# SYSTEM.net
KiCad netlist of a schematic drawn in Altium Designer
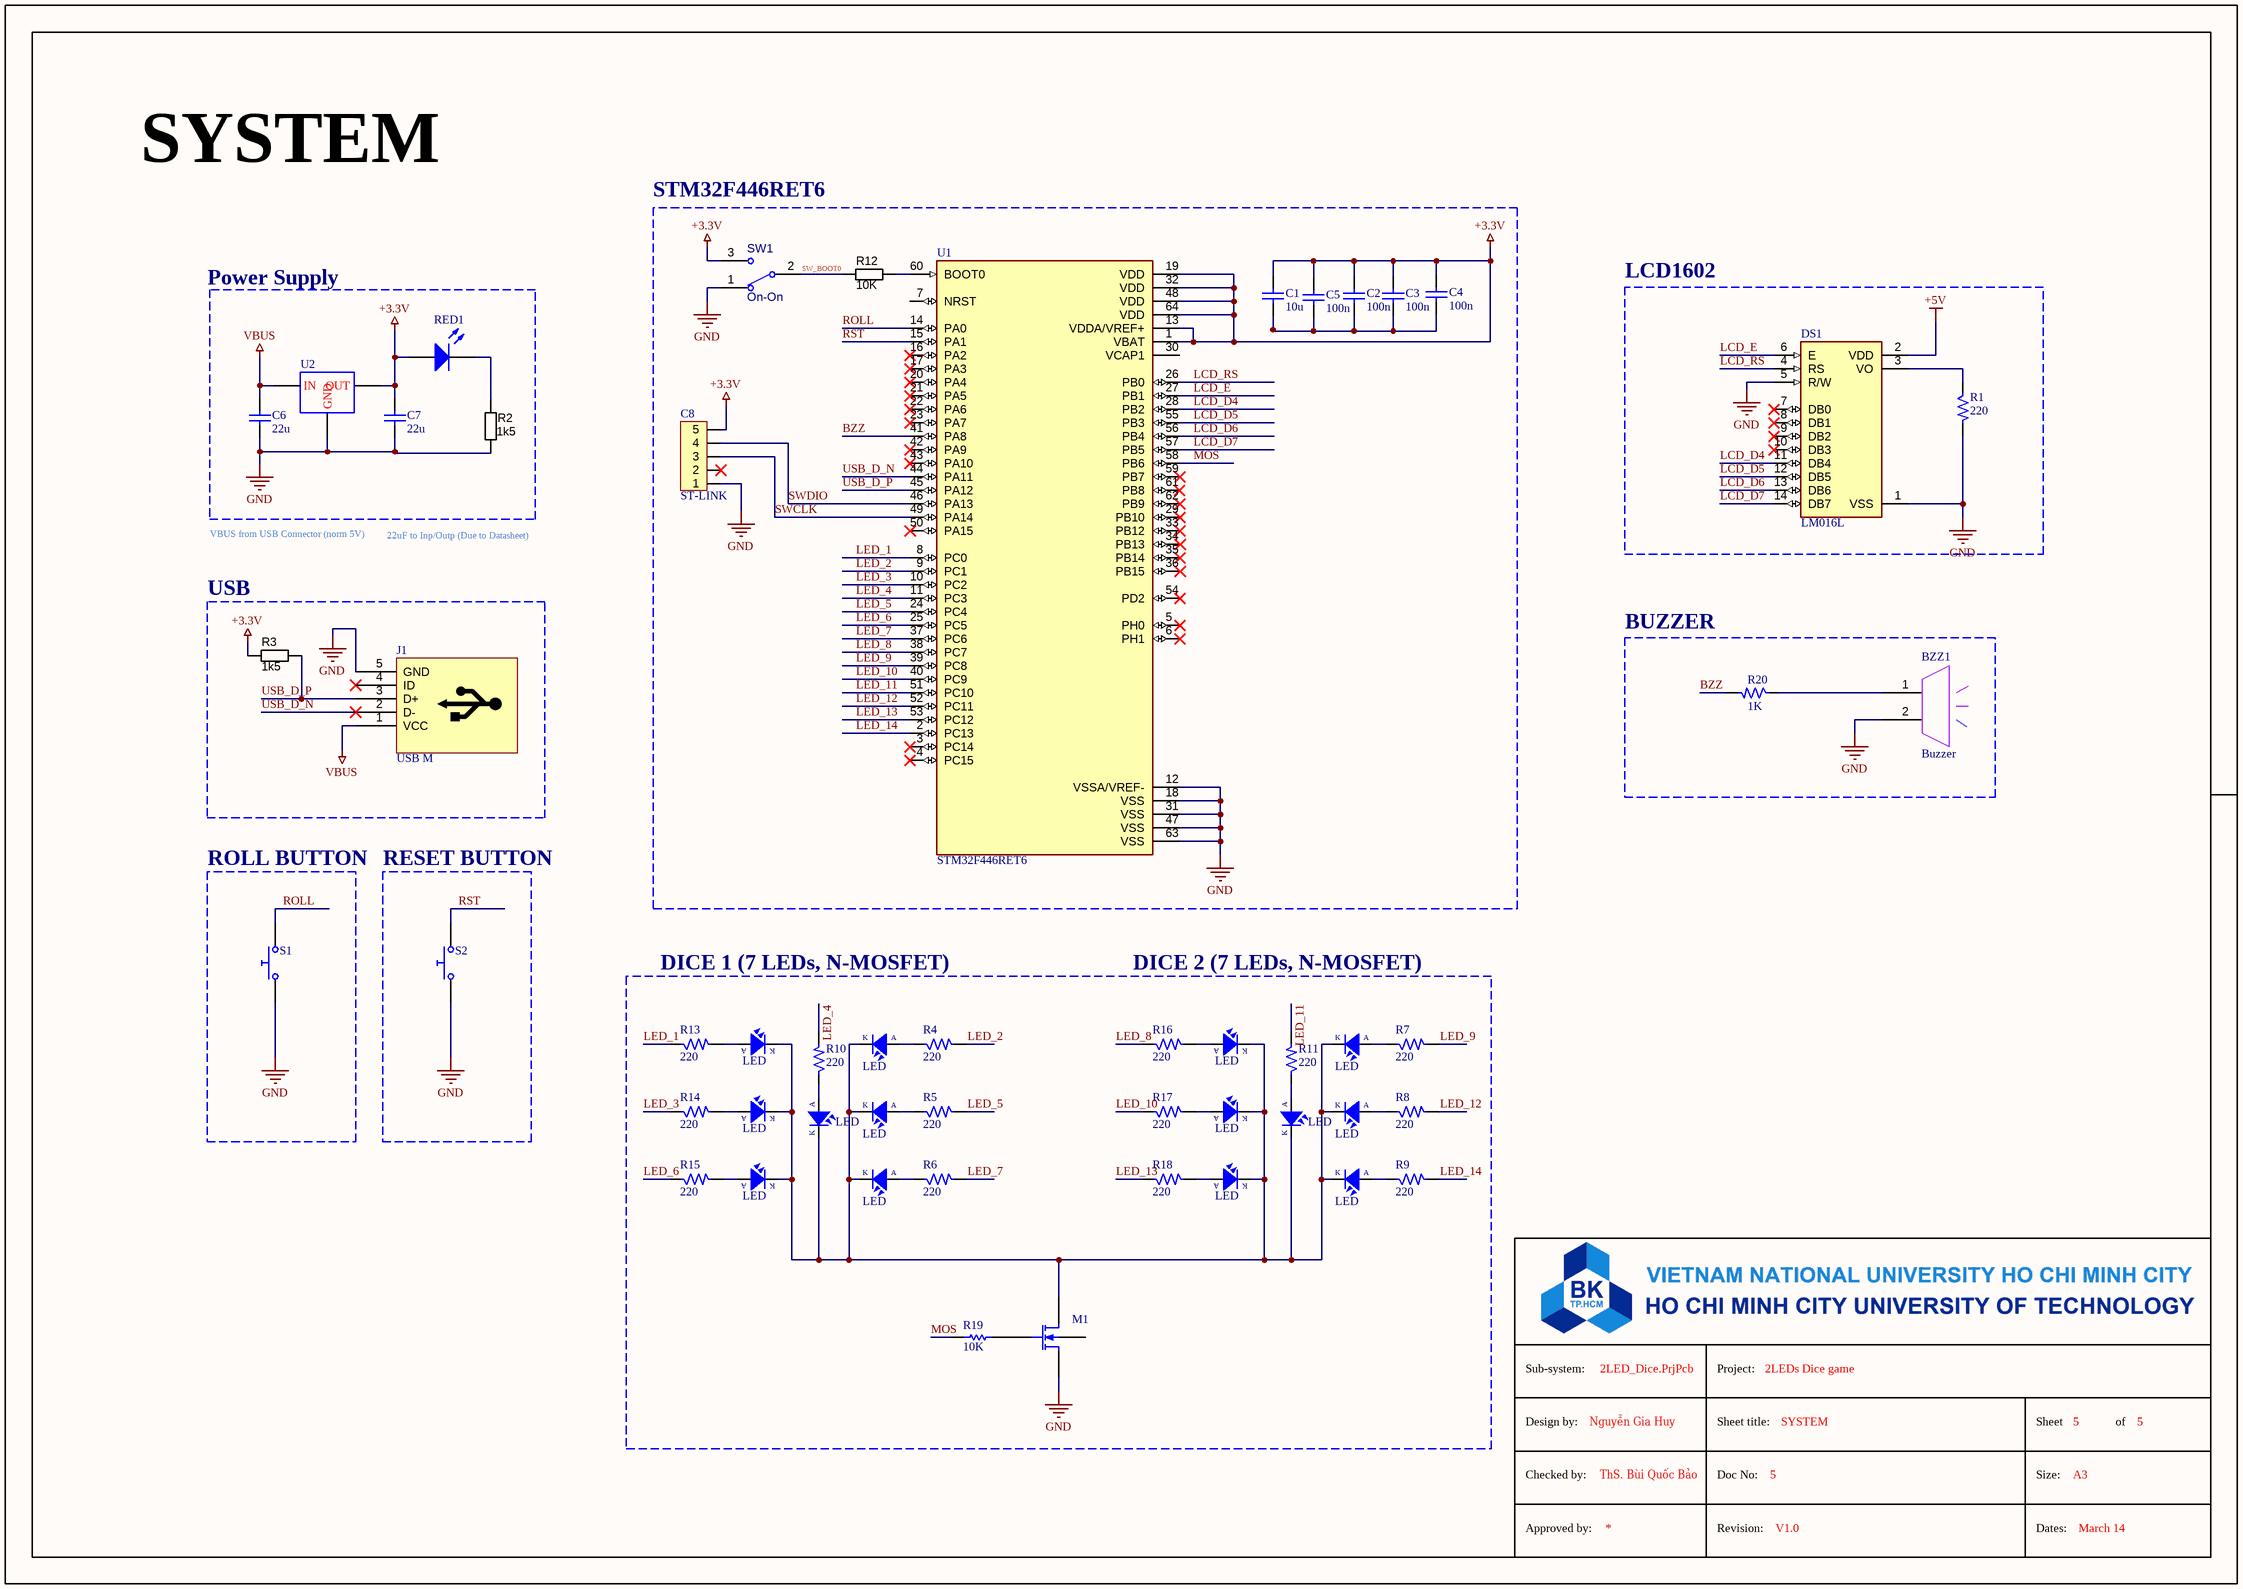
[diagram p0: SYSTEM.SchDoc]

(export (version "E")
  (design (tool "Eeschema 10.0.6"))
  (components
    (comp (ref "BZZ1")
      (value "Buzzer")
      (footprint "buzzer 5V")
      (libsource (lib "my Library") (part "Buzzer"))
    )
    (comp (ref "C1")
      (value "10u")
      (footprint "tu 0402")
      (description "Capacitor")
      (libsource (lib "Simulation Generic Components") (part "Capacitor"))
    )
    (comp (ref "C2")
      (value "100n")
      (footprint "tu 0402")
      (description "Capacitor")
      (libsource (lib "Simulation Generic Components") (part "Capacitor"))
    )
    (comp (ref "C3")
      (value "100n")
      (footprint "tu 0402")
      (description "Capacitor")
      (libsource (lib "Simulation Generic Components") (part "Capacitor"))
    )
    (comp (ref "C4")
      (value "100n")
      (footprint "tu 0402")
      (description "Capacitor")
      (libsource (lib "Simulation Generic Components") (part "Capacitor"))
    )
    (comp (ref "C5")
      (value "100n")
      (footprint "tu 0402")
      (description "Capacitor")
      (libsource (lib "Simulation Generic Components") (part "Capacitor"))
    )
    (comp (ref "C6")
      (value "22u")
      (footprint "CAPC2012X94N")
      (description "Capacitor")
      (libsource (lib "Simulation Generic Components") (part "Capacitor"))
    )
    (comp (ref "C7")
      (value "22u")
      (footprint "CAPC2012X94N")
      (description "Capacitor")
      (libsource (lib "Simulation Generic Components") (part "Capacitor"))
    )
    (comp (ref "C8")
      (value "ST-LINK")
      (footprint "HDR5")
      (description "Header IDC, 5 x 1 Pin Vertical 2.54mm Pitch (Non-Boxed, Male)")
      (fields
        (field (name "MANUFACTURER") "Würth Elektronik eiSos GmbH")
        (field (name "PARTNO") "613002143121")
        (field (name "CREATED BY") "Karrer Zheng")
      )
      (libsource (lib "LIBRARY") (part "Header5"))
    )
    (comp (ref "DS1")
      (value "LM016L")
      (footprint "MODULE_LCD-16X2")
      (description "Display Lcd 35x75mm")
      (fields (field (name "MF") "Hitachi"))
      (libsource (lib "LM016L") (part "LM016L"))
    )
    (comp (ref "J1")
      (value "USB M")
      (footprint "USB-Micr-B-FCI-SMD")
      (libsource (lib "my Library") (part "USB M"))
    )
    (comp (ref "LED1")
      (value "LED")
      (footprint "LED-3")
      (description "LED Single colour Green and Red")
      (libsource (lib "my Library") (part "LED"))
    )
    (comp (ref "LED2")
      (value "LED")
      (footprint "LED-3")
      (description "LED Single colour Green and Red")
      (libsource (lib "my Library") (part "LED"))
    )
    (comp (ref "LED3")
      (value "LED")
      (footprint "LED-3")
      (description "LED Single colour Green and Red")
      (libsource (lib "my Library") (part "LED"))
    )
    (comp (ref "LED4")
      (value "LED")
      (footprint "LED-3")
      (description "LED Single colour Green and Red")
      (libsource (lib "my Library") (part "LED"))
    )
    (comp (ref "LED5")
      (value "LED")
      (footprint "LED-3")
      (description "LED Single colour Green and Red")
      (libsource (lib "my Library") (part "LED"))
    )
    (comp (ref "LED6")
      (value "LED")
      (footprint "LED-3")
      (description "LED Single colour Green and Red")
      (libsource (lib "my Library") (part "LED"))
    )
    (comp (ref "LED7")
      (value "LED")
      (footprint "LED-3")
      (description "LED Single colour Green and Red")
      (libsource (lib "my Library") (part "LED"))
    )
    (comp (ref "LED8")
      (value "LED")
      (footprint "LED-3")
      (description "LED Single colour Green and Red")
      (libsource (lib "my Library") (part "LED"))
    )
    (comp (ref "LED9")
      (value "LED")
      (footprint "LED-3")
      (description "LED Single colour Green and Red")
      (libsource (lib "my Library") (part "LED"))
    )
    (comp (ref "LED10")
      (value "LED")
      (footprint "LED-3")
      (description "LED Single colour Green and Red")
      (libsource (lib "my Library") (part "LED"))
    )
    (comp (ref "LED11")
      (value "LED")
      (footprint "LED-3")
      (description "LED Single colour Green and Red")
      (libsource (lib "my Library") (part "LED"))
    )
    (comp (ref "LED12")
      (value "LED")
      (footprint "LED-3")
      (description "LED Single colour Green and Red")
      (libsource (lib "my Library") (part "LED"))
    )
    (comp (ref "LED13")
      (value "LED")
      (footprint "LED-3")
      (description "LED Single colour Green and Red")
      (libsource (lib "my Library") (part "LED"))
    )
    (comp (ref "LED14")
      (value "LED")
      (footprint "LED-3")
      (description "LED Single colour Green and Red")
      (libsource (lib "my Library") (part "LED"))
    )
    (comp (ref "M1")
      (value "N-channel MOS1 MOSFET Shichman and Hodges Model")
      (footprint "TO254P1054X469X1930-3")
      (libsource (lib "Simulation Generic Components") (part "MOSFET N-ch Lev1"))
    )
    (comp (ref "R1")
      (value "220")
      (footprint "RES-SMD-0402")
      (description "Res")
      (libsource (lib "my Library") (part "Res"))
    )
    (comp (ref "R2")
      (value "1k5")
      (footprint "RES-SMD-0402")
      (description "Resistor SMD chip 1k Ohm 0.063W 5% 0402")
      (fields (field (name "TOLERANCE") "±5%") (field (name "Comment") "Thick Film"))
      (libsource (lib "my Library") (part "RES_0402"))
    )
    (comp (ref "R3")
      (value "1k5")
      (footprint "RES-SMD-0402")
      (description "Resistor SMD chip 1k Ohm 0.063W 5% 0402")
      (fields (field (name "TOLERANCE") "±5%") (field (name "Comment") "Thick Film"))
      (libsource (lib "my Library") (part "RES_0402"))
    )
    (comp (ref "R4")
      (value "220")
      (footprint "RES-SMD-0402")
      (description "Res")
      (libsource (lib "my Library") (part "Res"))
    )
    (comp (ref "R5")
      (value "220")
      (footprint "RES-SMD-0402")
      (description "Res")
      (libsource (lib "my Library") (part "Res"))
    )
    (comp (ref "R6")
      (value "220")
      (footprint "RES-SMD-0402")
      (description "Res")
      (libsource (lib "my Library") (part "Res"))
    )
    (comp (ref "R7")
      (value "220")
      (footprint "RES-SMD-0402")
      (description "Res")
      (libsource (lib "my Library") (part "Res"))
    )
    (comp (ref "R8")
      (value "220")
      (footprint "RES-SMD-0402")
      (description "Res")
      (libsource (lib "my Library") (part "Res"))
    )
    (comp (ref "R9")
      (value "220")
      (footprint "RES-SMD-0402")
      (description "Res")
      (libsource (lib "my Library") (part "Res"))
    )
    (comp (ref "R10")
      (value "220")
      (footprint "RES-SMD-0402")
      (description "Res")
      (libsource (lib "my Library") (part "Res"))
    )
    (comp (ref "R11")
      (value "220")
      (footprint "RES-SMD-0402")
      (description "Res")
      (libsource (lib "my Library") (part "Res"))
    )
    (comp (ref "R12")
      (value "10K")
      (footprint "RES-SMD-0402")
      (description "Resistor SMD chip 1k Ohm 0.063W 5% 0402")
      (fields (field (name "TOLERANCE") "±5%") (field (name "Comment") "Thick Film"))
      (libsource (lib "") (part "RES_0402_1"))
    )
    (comp (ref "R13")
      (value "220")
      (footprint "RES-SMD-0402")
      (description "Res")
      (libsource (lib "my Library") (part "Res"))
    )
    (comp (ref "R14")
      (value "220")
      (footprint "RES-SMD-0402")
      (description "Res")
      (libsource (lib "my Library") (part "Res"))
    )
    (comp (ref "R15")
      (value "220")
      (footprint "RES-SMD-0402")
      (description "Res")
      (libsource (lib "my Library") (part "Res"))
    )
    (comp (ref "R16")
      (value "220")
      (footprint "RES-SMD-0402")
      (description "Res")
      (libsource (lib "my Library") (part "Res"))
    )
    (comp (ref "R17")
      (value "220")
      (footprint "RES-SMD-0402")
      (description "Res")
      (libsource (lib "my Library") (part "Res"))
    )
    (comp (ref "R18")
      (value "220")
      (footprint "RES-SMD-0402")
      (description "Res")
      (libsource (lib "my Library") (part "Res"))
    )
    (comp (ref "R19")
      (value "10K")
      (footprint "RES-SMD-0402")
      (description "Resistor")
      (libsource (lib "Simulation Generic Components") (part "Resistor"))
    )
    (comp (ref "R20")
      (value "1K")
      (footprint "RES-SMD-0402")
      (description "Res")
      (libsource (lib "my Library") (part "Res"))
    )
    (comp (ref "RED1")
      (value "Light-Emitting Diode")
      (footprint "LED-RED-0805")
      (libsource (lib "Simulation Generic Components") (part "LED"))
    )
    (comp (ref "S1")
      (value "Push Button Normally Opened")
      (footprint "SW4_SMD")
      (libsource (lib "Simulation Generic Components") (part "Push Button NO"))
    )
    (comp (ref "S2")
      (value "Push Button Normally Opened")
      (footprint "SW4_SMD")
      (libsource (lib "Simulation Generic Components") (part "Push Button NO"))
    )
    (comp (ref "SW1")
      (value "ON-ON")
      (footprint "SW4_SMD")
      (description "Switch THD vertical toggle SPDT")
      (fields (field (name "SWITCH FUNCTION") "On-On"))
      (libsource (lib "my Library") (part "SW_THD_SPDT_On-On"))
    )
    (comp (ref "U1")
      (value "STM32F446RET6")
      (footprint "QFP50P1200X1200X160-64N")
      (fields (field (name "MF") "STMicroelectronics") (field (name "MP") "STM32F401RET6TR"))
      (libsource (lib "STM32F401RET6TR") (part "STM32F401RET6TR"))
    )
    (comp (ref "U2")
      (value "Positive Fixed Voltage regulator")
      (footprint "AMS1117_3v3")
      (libsource (lib "Simulation Generic Components") (part "Linear Voltage Regulator (Fixed)"))
    )
  )
  (nets
    (net (code "1") (name "+3.3V") (class "Default")
      (node (ref "C1") (pin "1") (pinfunction "1_1") (pintype "passive"))
      (node (ref "C2") (pin "1") (pinfunction "1_1") (pintype "passive"))
      (node (ref "C3") (pin "1") (pinfunction "1_1") (pintype "passive"))
      (node (ref "C4") (pin "1") (pinfunction "1_1") (pintype "passive"))
      (node (ref "C5") (pin "1") (pinfunction "1_1") (pintype "passive"))
      (node (ref "C7") (pin "1") (pinfunction "1_1") (pintype "passive"))
      (node (ref "C8") (pin "5") (pinfunction "5_5") (pintype "passive"))
      (node (ref "R3") (pin "1") (pinfunction "1_1") (pintype "passive"))
      (node (ref "RED1") (pin "1") (pinfunction "A_1") (pintype "passive"))
      (node (ref "SW1") (pin "3") (pinfunction "3_3") (pintype "passive"))
      (node (ref "U1") (pin "1") (pinfunction "VBAT_1") (pintype "power_in"))
      (node (ref "U1") (pin "13") (pinfunction "VDDA/VREF+_13") (pintype "power_in"))
      (node (ref "U1") (pin "19") (pinfunction "VDD_19") (pintype "power_in"))
      (node (ref "U1") (pin "32") (pinfunction "VDD_32") (pintype "power_in"))
      (node (ref "U1") (pin "48") (pinfunction "VDD_48") (pintype "power_in"))
      (node (ref "U1") (pin "64") (pinfunction "VDD_64") (pintype "power_in"))
      (node (ref "U2") (pin "3") (pinfunction "OUT_3") (pintype "passive"))
    )
    (net (code "2") (name "+5V") (class "Default")
      (node (ref "DS1") (pin "2") (pinfunction "VDD_2") (pintype "power_in"))
    )
    (net (code "3") (name "/BZZ") (class "Default")
      (node (ref "R20") (pin "2") (pinfunction "2_2") (pintype "passive"))
      (node (ref "U1") (pin "41") (pinfunction "PA8_41") (pintype "bidirectional"))
    )
    (net (code "4") (name "/LCD_D4") (class "Default")
      (node (ref "DS1") (pin "11") (pinfunction "DB4_11") (pintype "bidirectional"))
      (node (ref "U1") (pin "28") (pinfunction "PB2_28") (pintype "bidirectional"))
    )
    (net (code "5") (name "/LCD_D5") (class "Default")
      (node (ref "DS1") (pin "12") (pinfunction "DB5_12") (pintype "bidirectional"))
      (node (ref "U1") (pin "55") (pinfunction "PB3_55") (pintype "bidirectional"))
    )
    (net (code "6") (name "/LCD_D6") (class "Default")
      (node (ref "DS1") (pin "13") (pinfunction "DB6_13") (pintype "bidirectional"))
      (node (ref "U1") (pin "56") (pinfunction "PB4_56") (pintype "bidirectional"))
    )
    (net (code "7") (name "/LCD_D7") (class "Default")
      (node (ref "DS1") (pin "14") (pinfunction "DB7_14") (pintype "bidirectional"))
      (node (ref "U1") (pin "57") (pinfunction "PB5_57") (pintype "bidirectional"))
    )
    (net (code "8") (name "/LCD_E") (class "Default")
      (node (ref "DS1") (pin "6") (pinfunction "E_6") (pintype "input"))
      (node (ref "U1") (pin "27") (pinfunction "PB1_27") (pintype "bidirectional"))
    )
    (net (code "9") (name "/LCD_RS") (class "Default")
      (node (ref "DS1") (pin "4") (pinfunction "RS_4") (pintype "input"))
      (node (ref "U1") (pin "26") (pinfunction "PB0_26") (pintype "bidirectional"))
    )
    (net (code "10") (name "/LED_1") (class "Default")
      (node (ref "R13") (pin "1") (pinfunction "1_1") (pintype "passive"))
      (node (ref "U1") (pin "8") (pinfunction "PC0_8") (pintype "bidirectional"))
    )
    (net (code "11") (name "/LED_2") (class "Default")
      (node (ref "R4") (pin "2") (pinfunction "2_2") (pintype "passive"))
      (node (ref "U1") (pin "9") (pinfunction "PC1_9") (pintype "bidirectional"))
    )
    (net (code "12") (name "/LED_3") (class "Default")
      (node (ref "R14") (pin "1") (pinfunction "1_1") (pintype "passive"))
      (node (ref "U1") (pin "10") (pinfunction "PC2_10") (pintype "bidirectional"))
    )
    (net (code "13") (name "/LED_4") (class "Default")
      (node (ref "R10") (pin "2") (pinfunction "2_2") (pintype "passive"))
      (node (ref "U1") (pin "11") (pinfunction "PC3_11") (pintype "bidirectional"))
    )
    (net (code "14") (name "/LED_5") (class "Default")
      (node (ref "R5") (pin "2") (pinfunction "2_2") (pintype "passive"))
      (node (ref "U1") (pin "24") (pinfunction "PC4_24") (pintype "bidirectional"))
    )
    (net (code "15") (name "/LED_6") (class "Default")
      (node (ref "R15") (pin "1") (pinfunction "1_1") (pintype "passive"))
      (node (ref "U1") (pin "25") (pinfunction "PC5_25") (pintype "bidirectional"))
    )
    (net (code "16") (name "/LED_7") (class "Default")
      (node (ref "R6") (pin "2") (pinfunction "2_2") (pintype "passive"))
      (node (ref "U1") (pin "37") (pinfunction "PC6_37") (pintype "bidirectional"))
    )
    (net (code "17") (name "/LED_8") (class "Default")
      (node (ref "R16") (pin "1") (pinfunction "1_1") (pintype "passive"))
      (node (ref "U1") (pin "38") (pinfunction "PC7_38") (pintype "bidirectional"))
    )
    (net (code "18") (name "/LED_9") (class "Default")
      (node (ref "R7") (pin "2") (pinfunction "2_2") (pintype "passive"))
      (node (ref "U1") (pin "39") (pinfunction "PC8_39") (pintype "bidirectional"))
    )
    (net (code "19") (name "/LED_10") (class "Default")
      (node (ref "R17") (pin "1") (pinfunction "1_1") (pintype "passive"))
      (node (ref "U1") (pin "40") (pinfunction "PC9_40") (pintype "bidirectional"))
    )
    (net (code "20") (name "/LED_11") (class "Default")
      (node (ref "R11") (pin "2") (pinfunction "2_2") (pintype "passive"))
      (node (ref "U1") (pin "51") (pinfunction "PC10_51") (pintype "bidirectional"))
    )
    (net (code "21") (name "/LED_12") (class "Default")
      (node (ref "R8") (pin "2") (pinfunction "2_2") (pintype "passive"))
      (node (ref "U1") (pin "52") (pinfunction "PC11_52") (pintype "bidirectional"))
    )
    (net (code "22") (name "/LED_13") (class "Default")
      (node (ref "R18") (pin "1") (pinfunction "1_1") (pintype "passive"))
      (node (ref "U1") (pin "53") (pinfunction "PC12_53") (pintype "bidirectional"))
    )
    (net (code "23") (name "/LED_14") (class "Default")
      (node (ref "R9") (pin "2") (pinfunction "2_2") (pintype "passive"))
      (node (ref "U1") (pin "2") (pinfunction "PC13_2") (pintype "bidirectional"))
    )
    (net (code "24") (name "/MOS") (class "Default")
      (node (ref "R19") (pin "2") (pinfunction "2_2") (pintype "passive"))
      (node (ref "U1") (pin "58") (pinfunction "PB6_58") (pintype "bidirectional"))
    )
    (net (code "25") (name "/ROLL") (class "Default")
      (node (ref "S1") (pin "2") (pinfunction "2_2") (pintype "passive"))
      (node (ref "U1") (pin "14") (pinfunction "PA0_14") (pintype "bidirectional"))
    )
    (net (code "26") (name "/RST") (class "Default")
      (node (ref "S2") (pin "2") (pinfunction "2_2") (pintype "passive"))
      (node (ref "U1") (pin "15") (pinfunction "PA1_15") (pintype "bidirectional"))
    )
    (net (code "27") (name "/SWCLK") (class "Default")
      (node (ref "C8") (pin "3") (pinfunction "3_3") (pintype "passive"))
      (node (ref "U1") (pin "49") (pinfunction "PA14_49") (pintype "bidirectional"))
    )
    (net (code "28") (name "/SWDIO") (class "Default")
      (node (ref "C8") (pin "4") (pinfunction "4_4") (pintype "passive"))
      (node (ref "U1") (pin "46") (pinfunction "PA13_46") (pintype "bidirectional"))
    )
    (net (code "29") (name "/SW_BOOT0") (class "Default")
      (node (ref "R12") (pin "2") (pinfunction "2_2") (pintype "passive"))
      (node (ref "SW1") (pin "2") (pinfunction "2_2") (pintype "passive"))
    )
    (net (code "30") (name "/USB_D_N") (class "Default")
      (node (ref "J1") (pin "2") (pinfunction "D-_2") (pintype "passive"))
      (node (ref "U1") (pin "44") (pinfunction "PA11_44") (pintype "bidirectional"))
    )
    (net (code "31") (name "/USB_D_P") (class "Default")
      (node (ref "J1") (pin "3") (pinfunction "D+_3") (pintype "passive"))
      (node (ref "R3") (pin "2") (pinfunction "2_2") (pintype "passive"))
      (node (ref "U1") (pin "45") (pinfunction "PA12_45") (pintype "bidirectional"))
    )
    (net (code "32") (name "GND") (class "Default")
      (node (ref "BZZ1") (pin "2") (pinfunction "2_2") (pintype "passive"))
      (node (ref "C6") (pin "2") (pinfunction "2_2") (pintype "passive"))
      (node (ref "C7") (pin "2") (pinfunction "2_2") (pintype "passive"))
      (node (ref "C8") (pin "1") (pinfunction "1_1") (pintype "passive"))
      (node (ref "DS1") (pin "1") (pinfunction "VSS_1") (pintype "power_in"))
      (node (ref "DS1") (pin "5") (pinfunction "R/W_5") (pintype "input"))
      (node (ref "J1") (pin "5") (pinfunction "GND_5") (pintype "passive"))
      (node (ref "M1") (pin "3") (pinfunction "S_3") (pintype "passive"))
      (node (ref "R1") (pin "2") (pinfunction "2_2") (pintype "passive"))
      (node (ref "R2") (pin "1") (pinfunction "1_1") (pintype "passive"))
      (node (ref "S1") (pin "1") (pinfunction "1_1") (pintype "passive"))
      (node (ref "S2") (pin "1") (pinfunction "1_1") (pintype "passive"))
      (node (ref "SW1") (pin "1") (pinfunction "1_1") (pintype "passive"))
      (node (ref "U1") (pin "12") (pinfunction "VSSA/VREF-_12") (pintype "power_in"))
      (node (ref "U1") (pin "18") (pinfunction "VSS_18") (pintype "power_in"))
      (node (ref "U1") (pin "31") (pinfunction "VSS_31") (pintype "power_in"))
      (node (ref "U1") (pin "47") (pinfunction "VSS_47") (pintype "power_in"))
      (node (ref "U1") (pin "63") (pinfunction "VSS_63") (pintype "power_in"))
      (node (ref "U2") (pin "2") (pinfunction "GND_2") (pintype "passive"))
    )
    (net (code "33") (name "Net-(BZZ1-Pad1)") (class "Default")
      (node (ref "BZZ1") (pin "1") (pinfunction "1_1") (pintype "passive"))
      (node (ref "R20") (pin "1") (pinfunction "1_1") (pintype "passive"))
    )
    (net (code "34") (name "Net-(C1-Pad2)") (class "Default")
      (node (ref "C1") (pin "2") (pinfunction "2_2") (pintype "passive"))
      (node (ref "C2") (pin "2") (pinfunction "2_2") (pintype "passive"))
      (node (ref "C3") (pin "2") (pinfunction "2_2") (pintype "passive"))
      (node (ref "C4") (pin "2") (pinfunction "2_2") (pintype "passive"))
      (node (ref "C5") (pin "2") (pinfunction "2_2") (pintype "passive"))
    )
    (net (code "35") (name "Net-(DS1-VO)") (class "Default")
      (node (ref "DS1") (pin "3") (pinfunction "VO_3") (pintype "power_in"))
      (node (ref "R1") (pin "1") (pinfunction "1_1") (pintype "passive"))
    )
    (net (code "36") (name "Net-(LED1-A)") (class "Default")
      (node (ref "LED1") (pin "1") (pinfunction "A_1") (pintype "passive"))
      (node (ref "R4") (pin "1") (pinfunction "1_1") (pintype "passive"))
    )
    (net (code "37") (name "Net-(LED1-K)") (class "Default")
      (node (ref "LED1") (pin "2") (pinfunction "K_2") (pintype "passive"))
      (node (ref "LED10") (pin "2") (pinfunction "K_2") (pintype "passive"))
      (node (ref "LED11") (pin "2") (pinfunction "K_2") (pintype "passive"))
      (node (ref "LED12") (pin "2") (pinfunction "K_2") (pintype "passive"))
      (node (ref "LED13") (pin "2") (pinfunction "K_2") (pintype "passive"))
      (node (ref "LED14") (pin "2") (pinfunction "K_2") (pintype "passive"))
      (node (ref "LED2") (pin "2") (pinfunction "K_2") (pintype "passive"))
      (node (ref "LED3") (pin "2") (pinfunction "K_2") (pintype "passive"))
      (node (ref "LED4") (pin "2") (pinfunction "K_2") (pintype "passive"))
      (node (ref "LED5") (pin "2") (pinfunction "K_2") (pintype "passive"))
      (node (ref "LED6") (pin "2") (pinfunction "K_2") (pintype "passive"))
      (node (ref "LED7") (pin "2") (pinfunction "K_2") (pintype "passive"))
      (node (ref "LED8") (pin "2") (pinfunction "K_2") (pintype "passive"))
      (node (ref "LED9") (pin "2") (pinfunction "K_2") (pintype "passive"))
      (node (ref "M1") (pin "1") (pinfunction "D_1") (pintype "passive"))
    )
    (net (code "38") (name "Net-(LED2-A)") (class "Default")
      (node (ref "LED2") (pin "1") (pinfunction "A_1") (pintype "passive"))
      (node (ref "R5") (pin "1") (pinfunction "1_1") (pintype "passive"))
    )
    (net (code "39") (name "Net-(LED3-A)") (class "Default")
      (node (ref "LED3") (pin "1") (pinfunction "A_1") (pintype "passive"))
      (node (ref "R6") (pin "1") (pinfunction "1_1") (pintype "passive"))
    )
    (net (code "40") (name "Net-(LED4-A)") (class "Default")
      (node (ref "LED4") (pin "1") (pinfunction "A_1") (pintype "passive"))
      (node (ref "R7") (pin "1") (pinfunction "1_1") (pintype "passive"))
    )
    (net (code "41") (name "Net-(LED5-A)") (class "Default")
      (node (ref "LED5") (pin "1") (pinfunction "A_1") (pintype "passive"))
      (node (ref "R8") (pin "1") (pinfunction "1_1") (pintype "passive"))
    )
    (net (code "42") (name "Net-(LED6-A)") (class "Default")
      (node (ref "LED6") (pin "1") (pinfunction "A_1") (pintype "passive"))
      (node (ref "R9") (pin "1") (pinfunction "1_1") (pintype "passive"))
    )
    (net (code "43") (name "Net-(LED7-A)") (class "Default")
      (node (ref "LED7") (pin "1") (pinfunction "A_1") (pintype "passive"))
      (node (ref "R10") (pin "1") (pinfunction "1_1") (pintype "passive"))
    )
    (net (code "44") (name "Net-(LED8-A)") (class "Default")
      (node (ref "LED8") (pin "1") (pinfunction "A_1") (pintype "passive"))
      (node (ref "R11") (pin "1") (pinfunction "1_1") (pintype "passive"))
    )
    (net (code "45") (name "Net-(LED9-A)") (class "Default")
      (node (ref "LED9") (pin "1") (pinfunction "A_1") (pintype "passive"))
      (node (ref "R13") (pin "2") (pinfunction "2_2") (pintype "passive"))
    )
    (net (code "46") (name "Net-(LED10-A)") (class "Default")
      (node (ref "LED10") (pin "1") (pinfunction "A_1") (pintype "passive"))
      (node (ref "R14") (pin "2") (pinfunction "2_2") (pintype "passive"))
    )
    (net (code "47") (name "Net-(LED11-A)") (class "Default")
      (node (ref "LED11") (pin "1") (pinfunction "A_1") (pintype "passive"))
      (node (ref "R15") (pin "2") (pinfunction "2_2") (pintype "passive"))
    )
    (net (code "48") (name "Net-(LED12-A)") (class "Default")
      (node (ref "LED12") (pin "1") (pinfunction "A_1") (pintype "passive"))
      (node (ref "R16") (pin "2") (pinfunction "2_2") (pintype "passive"))
    )
    (net (code "49") (name "Net-(LED13-A)") (class "Default")
      (node (ref "LED13") (pin "1") (pinfunction "A_1") (pintype "passive"))
      (node (ref "R17") (pin "2") (pinfunction "2_2") (pintype "passive"))
    )
    (net (code "50") (name "Net-(LED14-A)") (class "Default")
      (node (ref "LED14") (pin "1") (pinfunction "A_1") (pintype "passive"))
      (node (ref "R18") (pin "2") (pinfunction "2_2") (pintype "passive"))
    )
    (net (code "51") (name "Net-(M1-G)") (class "Default")
      (node (ref "M1") (pin "2") (pinfunction "G_2") (pintype "passive"))
      (node (ref "R19") (pin "1") (pinfunction "1_1") (pintype "passive"))
    )
    (net (code "52") (name "Net-(RED1-K)") (class "Default")
      (node (ref "R2") (pin "2") (pinfunction "2_2") (pintype "passive"))
      (node (ref "RED1") (pin "2") (pinfunction "K_2") (pintype "passive"))
    )
    (net (code "53") (name "Net-(U1-BOOT0)") (class "Default")
      (node (ref "R12") (pin "1") (pinfunction "1_1") (pintype "passive"))
      (node (ref "U1") (pin "60") (pinfunction "BOOT0_60") (pintype "input"))
    )
    (net (code "54") (name "VBUS") (class "Default")
      (node (ref "C6") (pin "1") (pinfunction "1_1") (pintype "passive"))
      (node (ref "J1") (pin "1") (pinfunction "VCC_1") (pintype "passive"))
      (node (ref "U2") (pin "1") (pinfunction "IN_1") (pintype "passive"))
    )
    (net (code "55") (name "unconnected-(C8-Pad2)") (class "Default")
      (node (ref "C8") (pin "2") (pinfunction "2_2") (pintype "passive+no_connect"))
    )
    (net (code "56") (name "unconnected-(DS1-DB0-Pad7)") (class "Default")
      (node (ref "DS1") (pin "7") (pinfunction "DB0_7") (pintype "bidirectional+no_connect"))
    )
    (net (code "57") (name "unconnected-(DS1-DB1-Pad8)") (class "Default")
      (node (ref "DS1") (pin "8") (pinfunction "DB1_8") (pintype "bidirectional+no_connect"))
    )
    (net (code "58") (name "unconnected-(DS1-DB2-Pad9)") (class "Default")
      (node (ref "DS1") (pin "9") (pinfunction "DB2_9") (pintype "bidirectional+no_connect"))
    )
    (net (code "59") (name "unconnected-(DS1-DB3-Pad10)") (class "Default")
      (node (ref "DS1") (pin "10") (pinfunction "DB3_10") (pintype "bidirectional+no_connect"))
    )
    (net (code "60") (name "unconnected-(J1-ID-Pad4)") (class "Default")
      (node (ref "J1") (pin "4") (pinfunction "ID_4") (pintype "passive+no_connect"))
    )
    (net (code "61") (name "unconnected-(M1-B-Pad4)") (class "Default")
      (node (ref "M1") (pin "4") (pinfunction "B_4") (pintype "passive"))
    )
    (net (code "62") (name "unconnected-(U1-NRST-Pad7)") (class "Default")
      (node (ref "U1") (pin "7") (pinfunction "NRST_7") (pintype "bidirectional"))
    )
    (net (code "63") (name "unconnected-(U1-PA2-Pad16)") (class "Default")
      (node (ref "U1") (pin "16") (pinfunction "PA2_16") (pintype "bidirectional+no_connect"))
    )
    (net (code "64") (name "unconnected-(U1-PA3-Pad17)") (class "Default")
      (node (ref "U1") (pin "17") (pinfunction "PA3_17") (pintype "bidirectional+no_connect"))
    )
    (net (code "65") (name "unconnected-(U1-PA4-Pad20)") (class "Default")
      (node (ref "U1") (pin "20") (pinfunction "PA4_20") (pintype "bidirectional+no_connect"))
    )
    (net (code "66") (name "unconnected-(U1-PA5-Pad21)") (class "Default")
      (node (ref "U1") (pin "21") (pinfunction "PA5_21") (pintype "bidirectional+no_connect"))
    )
    (net (code "67") (name "unconnected-(U1-PA6-Pad22)") (class "Default")
      (node (ref "U1") (pin "22") (pinfunction "PA6_22") (pintype "bidirectional+no_connect"))
    )
    (net (code "68") (name "unconnected-(U1-PA7-Pad23)") (class "Default")
      (node (ref "U1") (pin "23") (pinfunction "PA7_23") (pintype "bidirectional+no_connect"))
    )
    (net (code "69") (name "unconnected-(U1-PA9-Pad42)") (class "Default")
      (node (ref "U1") (pin "42") (pinfunction "PA9_42") (pintype "bidirectional+no_connect"))
    )
    (net (code "70") (name "unconnected-(U1-PA10-Pad43)") (class "Default")
      (node (ref "U1") (pin "43") (pinfunction "PA10_43") (pintype "bidirectional+no_connect"))
    )
    (net (code "71") (name "unconnected-(U1-PA15-Pad50)") (class "Default")
      (node (ref "U1") (pin "50") (pinfunction "PA15_50") (pintype "bidirectional"))
    )
    (net (code "72") (name "unconnected-(U1-PB7-Pad59)") (class "Default")
      (node (ref "U1") (pin "59") (pinfunction "PB7_59") (pintype "bidirectional+no_connect"))
    )
    (net (code "73") (name "unconnected-(U1-PB8-Pad61)") (class "Default")
      (node (ref "U1") (pin "61") (pinfunction "PB8_61") (pintype "bidirectional"))
    )
    (net (code "74") (name "unconnected-(U1-PB9-Pad62)") (class "Default")
      (node (ref "U1") (pin "62") (pinfunction "PB9_62") (pintype "bidirectional+no_connect"))
    )
    (net (code "75") (name "unconnected-(U1-PB10-Pad29)") (class "Default")
      (node (ref "U1") (pin "29") (pinfunction "PB10_29") (pintype "bidirectional+no_connect"))
    )
    (net (code "76") (name "unconnected-(U1-PB12-Pad33)") (class "Default")
      (node (ref "U1") (pin "33") (pinfunction "PB12_33") (pintype "bidirectional+no_connect"))
    )
    (net (code "77") (name "unconnected-(U1-PB13-Pad34)") (class "Default")
      (node (ref "U1") (pin "34") (pinfunction "PB13_34") (pintype "bidirectional"))
    )
    (net (code "78") (name "unconnected-(U1-PB14-Pad35)") (class "Default")
      (node (ref "U1") (pin "35") (pinfunction "PB14_35") (pintype "bidirectional+no_connect"))
    )
    (net (code "79") (name "unconnected-(U1-PB15-Pad36)") (class "Default")
      (node (ref "U1") (pin "36") (pinfunction "PB15_36") (pintype "bidirectional"))
    )
    (net (code "80") (name "unconnected-(U1-PC14-Pad3)") (class "Default")
      (node (ref "U1") (pin "3") (pinfunction "PC14_3") (pintype "bidirectional+no_connect"))
    )
    (net (code "81") (name "unconnected-(U1-PC15-Pad4)") (class "Default")
      (node (ref "U1") (pin "4") (pinfunction "PC15_4") (pintype "bidirectional+no_connect"))
    )
    (net (code "82") (name "unconnected-(U1-PD2-Pad54)") (class "Default")
      (node (ref "U1") (pin "54") (pinfunction "PD2_54") (pintype "bidirectional+no_connect"))
    )
    (net (code "83") (name "unconnected-(U1-PH0-Pad5)") (class "Default")
      (node (ref "U1") (pin "5") (pinfunction "PH0_5") (pintype "bidirectional+no_connect"))
    )
    (net (code "84") (name "unconnected-(U1-PH1-Pad6)") (class "Default")
      (node (ref "U1") (pin "6") (pinfunction "PH1_6") (pintype "bidirectional+no_connect"))
    )
    (net (code "85") (name "unconnected-(U1-VCAP1-Pad30)") (class "Default")
      (node (ref "U1") (pin "30") (pinfunction "VCAP1_30") (pintype "power_in"))
    )
  )
)
